# Sch1.net
KiCad netlist of a schematic drawn in EAGLE
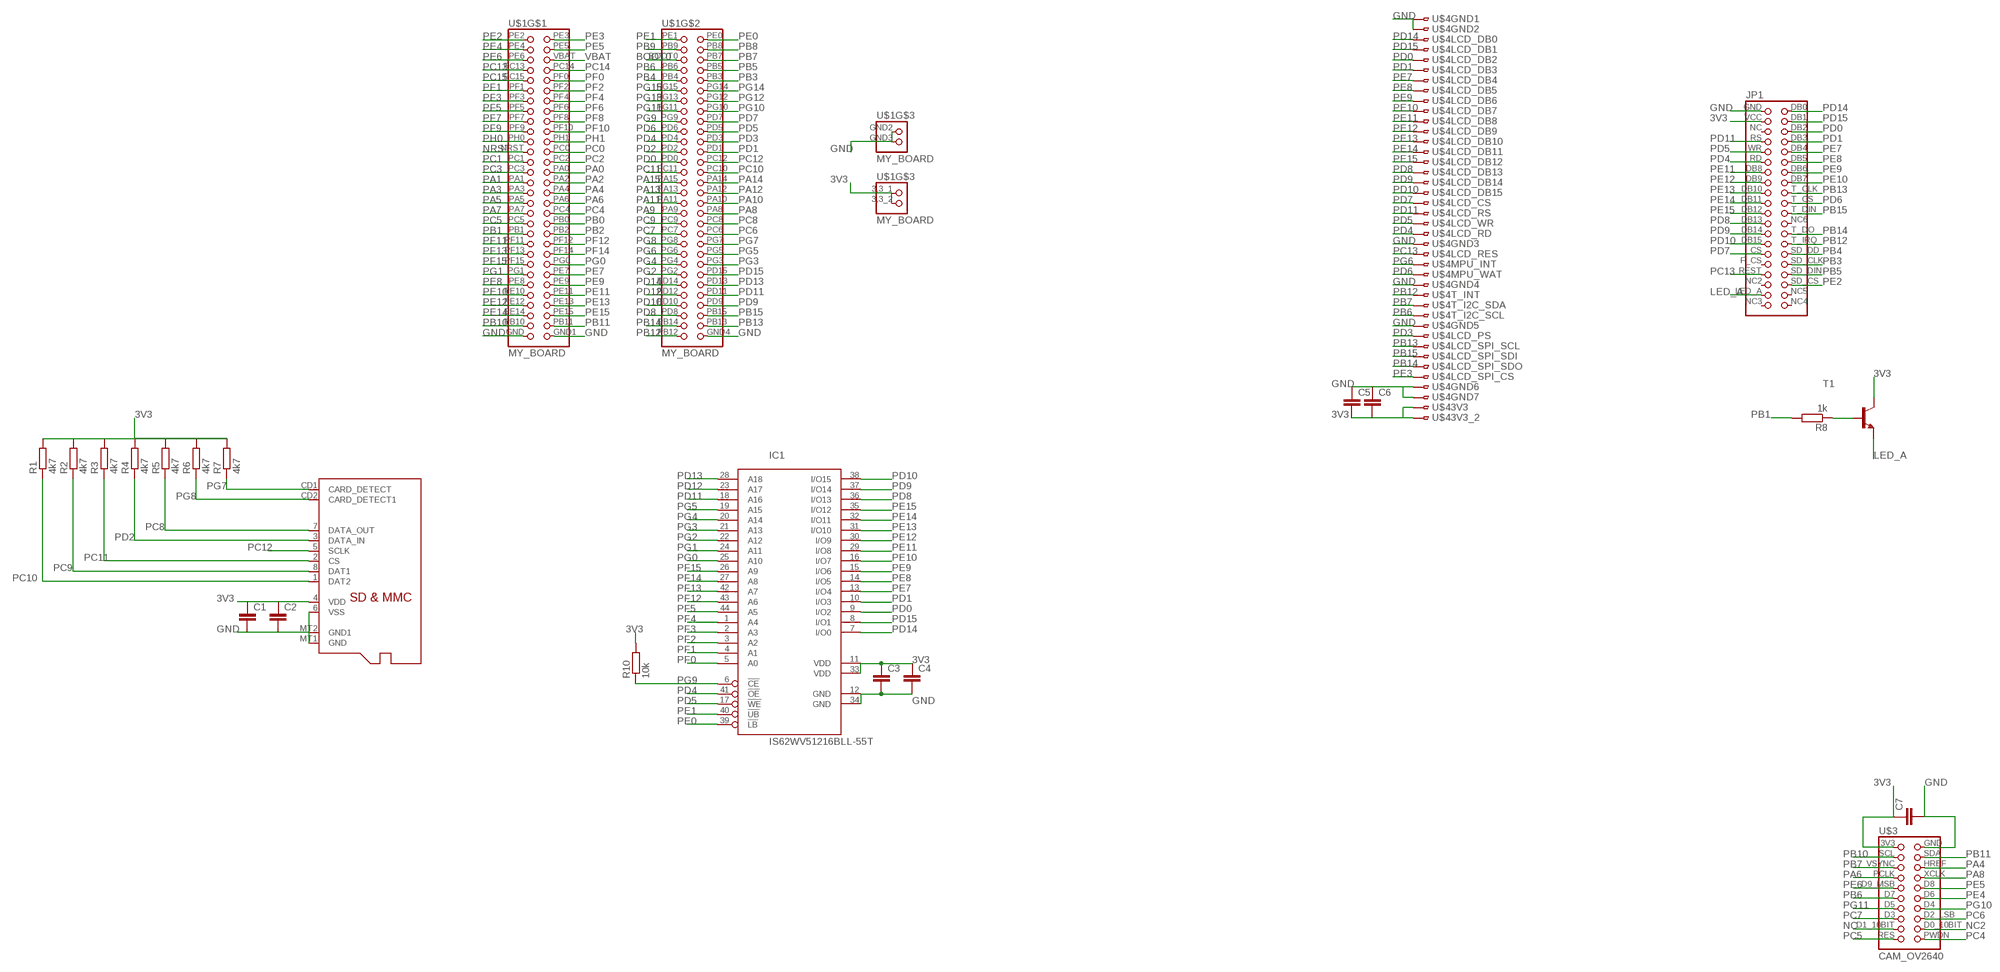
[diagram p0: schematic, sheet 1]

(export (version "E")
  (design (tool "Eeschema 10.0.6"))
  (components
    (comp (ref "C1")
      (value "C-EUC1206")
      (footprint "eagle-import:C1206")
      (libsource (lib "eagle-import") (part "C-EUC1206"))
    )
    (comp (ref "C2")
      (value "C-EUC1206")
      (footprint "eagle-import:C1206")
      (libsource (lib "eagle-import") (part "C-EUC1206"))
    )
    (comp (ref "C3")
      (value "C-EUC1206")
      (footprint "eagle-import:C1206")
      (libsource (lib "eagle-import") (part "C-EUC1206"))
    )
    (comp (ref "C4")
      (value "C-EUC1206")
      (footprint "eagle-import:C1206")
      (libsource (lib "eagle-import") (part "C-EUC1206"))
    )
    (comp (ref "C5")
      (value "C-EUC1206")
      (footprint "eagle-import:C1206")
      (libsource (lib "eagle-import") (part "C-EUC1206"))
    )
    (comp (ref "C6")
      (value "C-EUC1206")
      (footprint "eagle-import:C1206")
      (libsource (lib "eagle-import") (part "C-EUC1206"))
    )
    (comp (ref "C7")
      (value "C-EUC1206")
      (footprint "eagle-import:C1206")
      (libsource (lib "eagle-import") (part "C-EUC1206"))
    )
    (comp (ref "IC1")
      (value "IS62WV51216BLL-55T")
      (footprint "eagle-import:TSOP-II-44")
      (libsource (lib "eagle-import") (part "IS62WV51216BLL-T55"))
    )
    (comp (ref "JP1")
      (value "LCD320QVBLCD320QVB")
      (footprint "eagle-import:2X20")
      (libsource (lib "eagle-import") (part "LCD320QVBLCD320QVB"))
    )
    (comp (ref "R1")
      (value "4k7")
      (footprint "eagle-import:0204_7")
      (libsource (lib "eagle-import") (part "resistor_R-EU_0204/7"))
    )
    (comp (ref "R2")
      (value "4k7")
      (footprint "eagle-import:0204_7")
      (libsource (lib "eagle-import") (part "resistor_R-EU_0204/7"))
    )
    (comp (ref "R3")
      (value "4k7")
      (footprint "eagle-import:0204_7")
      (libsource (lib "eagle-import") (part "resistor_R-EU_0204/7"))
    )
    (comp (ref "R4")
      (value "4k7")
      (footprint "eagle-import:0204_7")
      (libsource (lib "eagle-import") (part "resistor_R-EU_0204/7"))
    )
    (comp (ref "R5")
      (value "4k7")
      (footprint "eagle-import:0204_7")
      (libsource (lib "eagle-import") (part "resistor_R-EU_0204/7"))
    )
    (comp (ref "R6")
      (value "4k7")
      (footprint "eagle-import:0204_7")
      (libsource (lib "eagle-import") (part "resistor_R-EU_0204/7"))
    )
    (comp (ref "R7")
      (value "4k7")
      (footprint "eagle-import:0204_7")
      (libsource (lib "eagle-import") (part "resistor_R-EU_0204/7"))
    )
    (comp (ref "R8")
      (value "1k")
      (footprint "eagle-import:0204_5")
      (libsource (lib "eagle-import") (part "R-EU_0204/5"))
    )
    (comp (ref "R10")
      (value "10k")
      (footprint "eagle-import:0204_7")
      (libsource (lib "eagle-import") (part "resistor_R-EU_0204/7"))
    )
    (comp (ref "T1")
      (value "BC337-NPN-TO92-CBE")
      (footprint "eagle-import:TO92-CBE")
      (libsource (lib "eagle-import") (part "-NPN-TO92-CBEBC337"))
    )
    (comp (ref "U$1")
      (value "MY_BOARD")
      (footprint "eagle-import:MY_BOARD")
      (libsource (lib "eagle-import") (part "MY_BOARD"))
    )
    (comp (ref "U$3")
      (value "CAM_OV2640")
      (footprint "eagle-import:CAM_OV2640")
      (libsource (lib "eagle-import") (part "CAM_OV2640"))
    )
    (comp (ref "U$4")
      (value "LCD800TFT")
      (footprint "eagle-import:FH12-40S-0.5SH")
      (libsource (lib "eagle-import") (part "LCD800TFT"))
    )
    (comp (ref "U$5")
      (value "MICROSD")
      (footprint "eagle-import:MICROSD")
      (libsource (lib "eagle-import") (part "MICROSD"))
    )
  )
  (nets
    (net (code "1") (name "/3V3") (class "Default")
      (node (ref "C1") (pin "1") (pinfunction "1_1") (pintype "passive"))
      (node (ref "C2") (pin "1") (pinfunction "1_1") (pintype "passive"))
      (node (ref "C3") (pin "1") (pinfunction "1_1") (pintype "passive"))
      (node (ref "C4") (pin "1") (pinfunction "1_1") (pintype "passive"))
      (node (ref "C5") (pin "2") (pinfunction "2_2") (pintype "passive"))
      (node (ref "C6") (pin "2") (pinfunction "2_2") (pintype "passive"))
      (node (ref "C7") (pin "1") (pinfunction "1_1") (pintype "passive"))
      (node (ref "IC1") (pin "11") (pinfunction "VDD_11") (pintype "power_in"))
      (node (ref "IC1") (pin "33") (pinfunction "VDD_33") (pintype "power_in"))
      (node (ref "JP1") (pin "VCC") (pinfunction "3_VCC") (pintype "passive"))
      (node (ref "R1") (pin "2") (pinfunction "2_2") (pintype "passive"))
      (node (ref "R10") (pin "2") (pinfunction "2_2") (pintype "passive"))
      (node (ref "R2") (pin "2") (pinfunction "2_2") (pintype "passive"))
      (node (ref "R3") (pin "2") (pinfunction "2_2") (pintype "passive"))
      (node (ref "R4") (pin "2") (pinfunction "2_2") (pintype "passive"))
      (node (ref "R5") (pin "2") (pinfunction "2_2") (pintype "passive"))
      (node (ref "R6") (pin "2") (pinfunction "2_2") (pintype "passive"))
      (node (ref "R7") (pin "2") (pinfunction "2_2") (pintype "passive"))
      (node (ref "T1") (pin "C") (pinfunction "C_C") (pintype "passive"))
      (node (ref "U$1") (pin "3,3_1") (pinfunction "1_3,3_1") (pintype "passive"))
      (node (ref "U$1") (pin "3,3_2") (pinfunction "2_3,3_2") (pintype "passive"))
      (node (ref "U$3") (pin "3V3") (pinfunction "3V3_3V3") (pintype "passive"))
      (node (ref "U$4") (pin "39") (pinfunction "1_39") (pintype "passive"))
      (node (ref "U$4") (pin "40") (pinfunction "1_40") (pintype "passive"))
      (node (ref "U$5") (pin "4") (pinfunction "VDD_4") (pintype "power_in"))
    )
    (net (code "2") (name "/BOOT0") (class "Default")
      (node (ref "U$1") (pin "BOOT0") (pinfunction "5_BOOT0") (pintype "passive"))
    )
    (net (code "3") (name "/GND") (class "Default")
      (node (ref "C1") (pin "2") (pinfunction "2_2") (pintype "passive"))
      (node (ref "C2") (pin "2") (pinfunction "2_2") (pintype "passive"))
      (node (ref "C3") (pin "2") (pinfunction "2_2") (pintype "passive"))
      (node (ref "C4") (pin "2") (pinfunction "2_2") (pintype "passive"))
      (node (ref "C5") (pin "1") (pinfunction "1_1") (pintype "passive"))
      (node (ref "C6") (pin "1") (pinfunction "1_1") (pintype "passive"))
      (node (ref "C7") (pin "2") (pinfunction "2_2") (pintype "passive"))
      (node (ref "IC1") (pin "12") (pinfunction "GND_12") (pintype "power_in"))
      (node (ref "IC1") (pin "34") (pinfunction "GND_34") (pintype "power_in"))
      (node (ref "JP1") (pin "GND") (pinfunction "1_GND") (pintype "passive"))
      (node (ref "U$1") (pin "GND") (pinfunction "59_GND") (pintype "passive"))
      (node (ref "U$1") (pin "GND1") (pinfunction "60_GND1") (pintype "passive"))
      (node (ref "U$1") (pin "GND2") (pinfunction "3_GND2") (pintype "passive"))
      (node (ref "U$1") (pin "GND3") (pinfunction "4_GND3") (pintype "passive"))
      (node (ref "U$1") (pin "GND4") (pinfunction "60_GND4") (pintype "passive"))
      (node (ref "U$3") (pin "GND") (pinfunction "GND_GND") (pintype "passive"))
      (node (ref "U$4") (pin "1") (pinfunction "1_1") (pintype "passive"))
      (node (ref "U$4") (pin "2") (pinfunction "1_2") (pintype "passive"))
      (node (ref "U$4") (pin "23") (pinfunction "1_23") (pintype "passive"))
      (node (ref "U$4") (pin "27") (pinfunction "1_27") (pintype "passive"))
      (node (ref "U$4") (pin "31") (pinfunction "1_31") (pintype "passive"))
      (node (ref "U$4") (pin "37") (pinfunction "1_37") (pintype "passive"))
      (node (ref "U$4") (pin "38") (pinfunction "1_38") (pintype "passive"))
      (node (ref "U$5") (pin "6") (pinfunction "VSS_6") (pintype "power_in"))
      (node (ref "U$5") (pin "MT1") (pinfunction "GND_MT1") (pintype "power_in"))
      (node (ref "U$5") (pin "MT2") (pinfunction "GND1_MT2") (pintype "power_in"))
    )
    (net (code "4") (name "/LED_A") (class "Default")
      (node (ref "JP1") (pin "LED_A") (pinfunction "37_LED_A") (pintype "passive"))
      (node (ref "T1") (pin "E") (pinfunction "E_E") (pintype "passive"))
    )
    (net (code "5") (name "/NC") (class "Default")
      (node (ref "U$3") (pin "D1_10BIT") (pinfunction "D1_10BIT_D1_10BIT") (pintype "passive"))
    )
    (net (code "6") (name "/NC2") (class "Default")
      (node (ref "U$3") (pin "D0_10BIT") (pinfunction "D0_10BIT_D0_10BIT") (pintype "passive"))
    )
    (net (code "7") (name "/NRST") (class "Default")
      (node (ref "U$1") (pin "NRST") (pinfunction "23_NRST") (pintype "passive"))
    )
    (net (code "8") (name "/PA0") (class "Default")
      (node (ref "U$1") (pin "PA0") (pinfunction "28_PA0") (pintype "passive"))
    )
    (net (code "9") (name "/PA1") (class "Default")
      (node (ref "U$1") (pin "PA1") (pinfunction "29_PA1") (pintype "passive"))
    )
    (net (code "10") (name "/PA2") (class "Default")
      (node (ref "U$1") (pin "PA2") (pinfunction "30_PA2") (pintype "passive"))
    )
    (net (code "11") (name "/PA3") (class "Default")
      (node (ref "U$1") (pin "PA3") (pinfunction "31_PA3") (pintype "passive"))
    )
    (net (code "12") (name "/PA4") (class "Default")
      (node (ref "U$1") (pin "PA4") (pinfunction "32_PA4") (pintype "passive"))
      (node (ref "U$3") (pin "HREF") (pinfunction "HREF_HREF") (pintype "passive"))
    )
    (net (code "13") (name "/PA5") (class "Default")
      (node (ref "U$1") (pin "PA5") (pinfunction "33_PA5") (pintype "passive"))
    )
    (net (code "14") (name "/PA6") (class "Default")
      (node (ref "U$1") (pin "PA6") (pinfunction "34_PA6") (pintype "passive"))
      (node (ref "U$3") (pin "PCLK") (pinfunction "PCLK_PCLK") (pintype "passive"))
    )
    (net (code "15") (name "/PA7") (class "Default")
      (node (ref "U$1") (pin "PA7") (pinfunction "35_PA7") (pintype "passive"))
    )
    (net (code "16") (name "/PA8") (class "Default")
      (node (ref "U$1") (pin "PA8") (pinfunction "36_PA8") (pintype "passive"))
      (node (ref "U$3") (pin "XCLK") (pinfunction "XCLK_XCLK") (pintype "passive"))
    )
    (net (code "17") (name "/PA9") (class "Default")
      (node (ref "U$1") (pin "PA9") (pinfunction "35_PA9") (pintype "passive"))
    )
    (net (code "18") (name "/PA10") (class "Default")
      (node (ref "U$1") (pin "PA10") (pinfunction "34_PA10") (pintype "passive"))
    )
    (net (code "19") (name "/PA11") (class "Default")
      (node (ref "U$1") (pin "PA11") (pinfunction "33_PA11") (pintype "passive"))
    )
    (net (code "20") (name "/PA12") (class "Default")
      (node (ref "U$1") (pin "PA12") (pinfunction "32_PA12") (pintype "passive"))
    )
    (net (code "21") (name "/PA13") (class "Default")
      (node (ref "U$1") (pin "PA13") (pinfunction "31_PA13") (pintype "passive"))
    )
    (net (code "22") (name "/PA14") (class "Default")
      (node (ref "U$1") (pin "PA14") (pinfunction "30_PA14") (pintype "passive"))
    )
    (net (code "23") (name "/PA15") (class "Default")
      (node (ref "U$1") (pin "PA15") (pinfunction "29_PA15") (pintype "passive"))
    )
    (net (code "24") (name "/PB0") (class "Default")
      (node (ref "U$1") (pin "PB0") (pinfunction "38_PB0") (pintype "passive"))
    )
    (net (code "25") (name "/PB1") (class "Default")
      (node (ref "R8") (pin "2") (pinfunction "2_2") (pintype "passive"))
      (node (ref "U$1") (pin "PB1") (pinfunction "39_PB1") (pintype "passive"))
    )
    (net (code "26") (name "/PB2") (class "Default")
      (node (ref "U$1") (pin "PB2") (pinfunction "40_PB2") (pintype "passive"))
    )
    (net (code "27") (name "/PB3") (class "Default")
      (node (ref "JP1") (pin "SD_CLK") (pinfunction "32_SD_CLK") (pintype "passive"))
      (node (ref "U$1") (pin "PB3") (pinfunction "10_PB3") (pintype "passive"))
    )
    (net (code "28") (name "/PB4") (class "Default")
      (node (ref "JP1") (pin "SD_DD") (pinfunction "30_SD_DD") (pintype "passive"))
      (node (ref "U$1") (pin "PB4") (pinfunction "9_PB4") (pintype "passive"))
    )
    (net (code "29") (name "/PB5") (class "Default")
      (node (ref "JP1") (pin "SD_DIN") (pinfunction "34_SD_DIN") (pintype "passive"))
      (node (ref "U$1") (pin "PB5") (pinfunction "8_PB5") (pintype "passive"))
    )
    (net (code "30") (name "/PB6") (class "Default")
      (node (ref "U$1") (pin "PB6") (pinfunction "7_PB6") (pintype "passive"))
      (node (ref "U$3") (pin "D7") (pinfunction "D7_D7") (pintype "passive"))
      (node (ref "U$4") (pin "30") (pinfunction "1_30") (pintype "passive"))
    )
    (net (code "31") (name "/PB7") (class "Default")
      (node (ref "U$1") (pin "PB7") (pinfunction "6_PB7") (pintype "passive"))
      (node (ref "U$3") (pin "VSYNC") (pinfunction "VSYNC_VSYNC") (pintype "passive"))
      (node (ref "U$4") (pin "29") (pinfunction "1_29") (pintype "passive"))
    )
    (net (code "32") (name "/PB8") (class "Default")
      (node (ref "U$1") (pin "PB8") (pinfunction "4_PB8") (pintype "passive"))
    )
    (net (code "33") (name "/PB9") (class "Default")
      (node (ref "U$1") (pin "PB9") (pinfunction "3_PB9") (pintype "passive"))
    )
    (net (code "34") (name "/PB10") (class "Default")
      (node (ref "U$1") (pin "PB10") (pinfunction "57_PB10") (pintype "passive"))
      (node (ref "U$3") (pin "SCL") (pinfunction "SCL_SCL") (pintype "passive"))
    )
    (net (code "35") (name "/PB11") (class "Default")
      (node (ref "U$1") (pin "PB11") (pinfunction "58_PB11") (pintype "passive"))
      (node (ref "U$3") (pin "SDA") (pinfunction "SDA_SDA") (pintype "passive"))
    )
    (net (code "36") (name "/PB12") (class "Default")
      (node (ref "JP1") (pin "T_IRQ") (pinfunction "28_T_IRQ") (pintype "passive"))
      (node (ref "U$1") (pin "PB12") (pinfunction "59_PB12") (pintype "passive"))
      (node (ref "U$4") (pin "28") (pinfunction "1_28") (pintype "passive"))
    )
    (net (code "37") (name "/PB13") (class "Default")
      (node (ref "JP1") (pin "T_CLK") (pinfunction "18_T_CLK") (pintype "passive"))
      (node (ref "U$1") (pin "PB13") (pinfunction "58_PB13") (pintype "passive"))
      (node (ref "U$4") (pin "33") (pinfunction "1_33") (pintype "passive"))
    )
    (net (code "38") (name "/PB14") (class "Default")
      (node (ref "JP1") (pin "T_DO") (pinfunction "26_T_DO") (pintype "passive"))
      (node (ref "U$1") (pin "PB14") (pinfunction "57_PB14") (pintype "passive"))
      (node (ref "U$4") (pin "35") (pinfunction "1_35") (pintype "passive"))
    )
    (net (code "39") (name "/PB15") (class "Default")
      (node (ref "JP1") (pin "T_DIN") (pinfunction "22_T_DIN") (pintype "passive"))
      (node (ref "U$1") (pin "PB15") (pinfunction "56_PB15") (pintype "passive"))
      (node (ref "U$4") (pin "34") (pinfunction "1_34") (pintype "passive"))
    )
    (net (code "40") (name "/PC0") (class "Default")
      (node (ref "U$1") (pin "PC0") (pinfunction "24_PC0") (pintype "passive"))
    )
    (net (code "41") (name "/PC1") (class "Default")
      (node (ref "U$1") (pin "PC1") (pinfunction "25_PC1") (pintype "passive"))
    )
    (net (code "42") (name "/PC2") (class "Default")
      (node (ref "U$1") (pin "PC2") (pinfunction "26_PC2") (pintype "passive"))
    )
    (net (code "43") (name "/PC3") (class "Default")
      (node (ref "U$1") (pin "PC3") (pinfunction "27_PC3") (pintype "passive"))
    )
    (net (code "44") (name "/PC4") (class "Default")
      (node (ref "U$1") (pin "PC4") (pinfunction "36_PC4") (pintype "passive"))
      (node (ref "U$3") (pin "PWDN") (pinfunction "PWDN_PWDN") (pintype "passive"))
    )
    (net (code "45") (name "/PC5") (class "Default")
      (node (ref "U$1") (pin "PC5") (pinfunction "37_PC5") (pintype "passive"))
      (node (ref "U$3") (pin "RES") (pinfunction "RES_RES") (pintype "passive"))
    )
    (net (code "46") (name "/PC6") (class "Default")
      (node (ref "U$1") (pin "PC6") (pinfunction "40_PC6") (pintype "passive"))
      (node (ref "U$3") (pin "D2_LSB") (pinfunction "D2_LSB_D2_LSB") (pintype "passive"))
    )
    (net (code "47") (name "/PC7") (class "Default")
      (node (ref "U$1") (pin "PC7") (pinfunction "39_PC7") (pintype "passive"))
      (node (ref "U$3") (pin "D3") (pinfunction "D3_D3") (pintype "passive"))
    )
    (net (code "48") (name "/PC8") (class "Default")
      (node (ref "R5") (pin "1") (pinfunction "1_1") (pintype "passive"))
      (node (ref "U$1") (pin "PC8") (pinfunction "38_PC8") (pintype "passive"))
      (node (ref "U$5") (pin "7") (pinfunction "DATA_OUT_7") (pintype "output"))
    )
    (net (code "49") (name "/PC9") (class "Default")
      (node (ref "R2") (pin "1") (pinfunction "1_1") (pintype "passive"))
      (node (ref "U$1") (pin "PC9") (pinfunction "37_PC9") (pintype "passive"))
      (node (ref "U$5") (pin "8") (pinfunction "DAT1_8") (pintype "bidirectional"))
    )
    (net (code "50") (name "/PC10") (class "Default")
      (node (ref "R1") (pin "1") (pinfunction "1_1") (pintype "passive"))
      (node (ref "U$1") (pin "PC10") (pinfunction "28_PC10") (pintype "passive"))
      (node (ref "U$5") (pin "1") (pinfunction "DAT2_1") (pintype "bidirectional"))
    )
    (net (code "51") (name "/PC11") (class "Default")
      (node (ref "R3") (pin "1") (pinfunction "1_1") (pintype "passive"))
      (node (ref "U$1") (pin "PC11") (pinfunction "27_PC11") (pintype "passive"))
      (node (ref "U$5") (pin "2") (pinfunction "CS_2") (pintype "input"))
    )
    (net (code "52") (name "/PC12") (class "Default")
      (node (ref "U$1") (pin "PC12") (pinfunction "26_PC12") (pintype "passive"))
      (node (ref "U$5") (pin "5") (pinfunction "SCLK_5") (pintype "input"))
    )
    (net (code "53") (name "/PC13") (class "Default")
      (node (ref "JP1") (pin "REST") (pinfunction "33_REST") (pintype "passive"))
      (node (ref "U$1") (pin "PC13") (pinfunction "7_PC13") (pintype "passive"))
      (node (ref "U$4") (pin "24") (pinfunction "1_24") (pintype "passive"))
    )
    (net (code "54") (name "/PC14") (class "Default")
      (node (ref "U$1") (pin "PC14") (pinfunction "8_PC14") (pintype "passive"))
    )
    (net (code "55") (name "/PC15") (class "Default")
      (node (ref "U$1") (pin "PC15") (pinfunction "9_PC15") (pintype "passive"))
    )
    (net (code "56") (name "/PD0") (class "Default")
      (node (ref "IC1") (pin "9") (pinfunction "I/O2_9") (pintype "tri_state"))
      (node (ref "JP1") (pin "DB2") (pinfunction "6_DB2") (pintype "passive"))
      (node (ref "U$1") (pin "PD0") (pinfunction "25_PD0") (pintype "passive"))
      (node (ref "U$4") (pin "5") (pinfunction "1_5") (pintype "passive"))
    )
    (net (code "57") (name "/PD1") (class "Default")
      (node (ref "IC1") (pin "10") (pinfunction "I/O3_10") (pintype "tri_state"))
      (node (ref "JP1") (pin "DB3") (pinfunction "8_DB3") (pintype "passive"))
      (node (ref "U$1") (pin "PD1") (pinfunction "24_PD1") (pintype "passive"))
      (node (ref "U$4") (pin "6") (pinfunction "1_6") (pintype "passive"))
    )
    (net (code "58") (name "/PD2") (class "Default")
      (node (ref "R4") (pin "1") (pinfunction "1_1") (pintype "passive"))
      (node (ref "U$1") (pin "PD2") (pinfunction "23_PD2") (pintype "passive"))
      (node (ref "U$5") (pin "3") (pinfunction "DATA_IN_3") (pintype "input"))
    )
    (net (code "59") (name "/PD3") (class "Default")
      (node (ref "U$1") (pin "PD3") (pinfunction "22_PD3") (pintype "passive"))
      (node (ref "U$4") (pin "32") (pinfunction "1_32") (pintype "passive"))
    )
    (net (code "60") (name "/PD4") (class "Default")
      (node (ref "IC1") (pin "41") (pinfunction "~{OE}_41") (pintype "input"))
      (node (ref "JP1") (pin "RD") (pinfunction "11_RD") (pintype "passive"))
      (node (ref "U$1") (pin "PD4") (pinfunction "21_PD4") (pintype "passive"))
      (node (ref "U$4") (pin "22") (pinfunction "1_22") (pintype "passive"))
    )
    (net (code "61") (name "/PD5") (class "Default")
      (node (ref "IC1") (pin "17") (pinfunction "~{WE}_17") (pintype "input"))
      (node (ref "JP1") (pin "WR") (pinfunction "9_WR") (pintype "passive"))
      (node (ref "U$1") (pin "PD5") (pinfunction "20_PD5") (pintype "passive"))
      (node (ref "U$4") (pin "21") (pinfunction "1_21") (pintype "passive"))
    )
    (net (code "62") (name "/PD6") (class "Default")
      (node (ref "JP1") (pin "T_CS") (pinfunction "20_T_CS") (pintype "passive"))
      (node (ref "U$1") (pin "PD6") (pinfunction "19_PD6") (pintype "passive"))
      (node (ref "U$4") (pin "26") (pinfunction "1_26") (pintype "passive"))
    )
    (net (code "63") (name "/PD7") (class "Default")
      (node (ref "JP1") (pin "CS") (pinfunction "29_CS") (pintype "passive"))
      (node (ref "U$1") (pin "PD7") (pinfunction "18_PD7") (pintype "passive"))
      (node (ref "U$4") (pin "19") (pinfunction "1_19") (pintype "passive"))
    )
    (net (code "64") (name "/PD8") (class "Default")
      (node (ref "IC1") (pin "36") (pinfunction "I/O13_36") (pintype "tri_state"))
      (node (ref "JP1") (pin "DB13") (pinfunction "23_DB13") (pintype "passive"))
      (node (ref "U$1") (pin "PD8") (pinfunction "55_PD8") (pintype "passive"))
      (node (ref "U$4") (pin "16") (pinfunction "1_16") (pintype "passive"))
    )
    (net (code "65") (name "/PD9") (class "Default")
      (node (ref "IC1") (pin "37") (pinfunction "I/O14_37") (pintype "tri_state"))
      (node (ref "JP1") (pin "DB14") (pinfunction "25_DB14") (pintype "passive"))
      (node (ref "U$1") (pin "PD9") (pinfunction "54_PD9") (pintype "passive"))
      (node (ref "U$4") (pin "17") (pinfunction "1_17") (pintype "passive"))
    )
    (net (code "66") (name "/PD10") (class "Default")
      (node (ref "IC1") (pin "38") (pinfunction "I/O15_38") (pintype "tri_state"))
      (node (ref "JP1") (pin "DB15") (pinfunction "27_DB15") (pintype "passive"))
      (node (ref "U$1") (pin "PD10") (pinfunction "53_PD10") (pintype "passive"))
      (node (ref "U$4") (pin "18") (pinfunction "1_18") (pintype "passive"))
    )
    (net (code "67") (name "/PD11") (class "Default")
      (node (ref "IC1") (pin "18") (pinfunction "A16_18") (pintype "input"))
      (node (ref "JP1") (pin "RS") (pinfunction "7_RS") (pintype "passive"))
      (node (ref "U$1") (pin "PD11") (pinfunction "52_PD11") (pintype "passive"))
      (node (ref "U$4") (pin "20") (pinfunction "1_20") (pintype "passive"))
    )
    (net (code "68") (name "/PD12") (class "Default")
      (node (ref "IC1") (pin "23") (pinfunction "A17_23") (pintype "input"))
      (node (ref "U$1") (pin "PD12") (pinfunction "51_PD12") (pintype "passive"))
    )
    (net (code "69") (name "/PD13") (class "Default")
      (node (ref "IC1") (pin "28") (pinfunction "A18_28") (pintype "input"))
      (node (ref "U$1") (pin "PD13") (pinfunction "50_PD13") (pintype "passive"))
    )
    (net (code "70") (name "/PD14") (class "Default")
      (node (ref "IC1") (pin "7") (pinfunction "I/O0_7") (pintype "tri_state"))
      (node (ref "JP1") (pin "DB0") (pinfunction "2_DB0") (pintype "passive"))
      (node (ref "U$1") (pin "PD14") (pinfunction "49_PD14") (pintype "passive"))
      (node (ref "U$4") (pin "3") (pinfunction "1_3") (pintype "passive"))
    )
    (net (code "71") (name "/PD15") (class "Default")
      (node (ref "IC1") (pin "8") (pinfunction "I/O1_8") (pintype "tri_state"))
      (node (ref "JP1") (pin "DB1") (pinfunction "4_DB1") (pintype "passive"))
      (node (ref "U$1") (pin "PD15") (pinfunction "48_PD15") (pintype "passive"))
      (node (ref "U$4") (pin "4") (pinfunction "1_4") (pintype "passive"))
    )
    (net (code "72") (name "/PE0") (class "Default")
      (node (ref "IC1") (pin "39") (pinfunction "~{LB}_39") (pintype "input"))
      (node (ref "U$1") (pin "PE0") (pinfunction "2_PE0") (pintype "passive"))
    )
    (net (code "73") (name "/PE1") (class "Default")
      (node (ref "IC1") (pin "40") (pinfunction "~{UB}_40") (pintype "input"))
      (node (ref "U$1") (pin "PE1") (pinfunction "1_PE1") (pintype "passive"))
    )
    (net (code "74") (name "/PE2") (class "Default")
      (node (ref "JP1") (pin "SD_CS") (pinfunction "36_SD_CS") (pintype "passive"))
      (node (ref "U$1") (pin "PE2") (pinfunction "1_PE2") (pintype "passive"))
    )
    (net (code "75") (name "/PE3") (class "Default")
      (node (ref "U$1") (pin "PE3") (pinfunction "2_PE3") (pintype "passive"))
      (node (ref "U$4") (pin "36") (pinfunction "1_36") (pintype "passive"))
    )
    (net (code "76") (name "/PE4") (class "Default")
      (node (ref "U$1") (pin "PE4") (pinfunction "3_PE4") (pintype "passive"))
      (node (ref "U$3") (pin "D6") (pinfunction "D6_D6") (pintype "passive"))
    )
    (net (code "77") (name "/PE5") (class "Default")
      (node (ref "U$1") (pin "PE5") (pinfunction "4_PE5") (pintype "passive"))
      (node (ref "U$3") (pin "D8") (pinfunction "D8_D8") (pintype "passive"))
    )
    (net (code "78") (name "/PE6") (class "Default")
      (node (ref "U$1") (pin "PE6") (pinfunction "5_PE6") (pintype "passive"))
      (node (ref "U$3") (pin "D9_MSB") (pinfunction "D9_MSB_D9_MSB") (pintype "passive"))
    )
    (net (code "79") (name "/PE7") (class "Default")
      (node (ref "IC1") (pin "13") (pinfunction "I/O4_13") (pintype "tri_state"))
      (node (ref "JP1") (pin "DB4") (pinfunction "10_DB4") (pintype "passive"))
      (node (ref "U$1") (pin "PE7") (pinfunction "48_PE7") (pintype "passive"))
      (node (ref "U$4") (pin "7") (pinfunction "1_7") (pintype "passive"))
    )
    (net (code "80") (name "/PE8") (class "Default")
      (node (ref "IC1") (pin "14") (pinfunction "I/O5_14") (pintype "tri_state"))
      (node (ref "JP1") (pin "DB5") (pinfunction "12_DB5") (pintype "passive"))
      (node (ref "U$1") (pin "PE8") (pinfunction "49_PE8") (pintype "passive"))
      (node (ref "U$4") (pin "8") (pinfunction "1_8") (pintype "passive"))
    )
    (net (code "81") (name "/PE9") (class "Default")
      (node (ref "IC1") (pin "15") (pinfunction "I/O6_15") (pintype "tri_state"))
      (node (ref "JP1") (pin "DB6") (pinfunction "14_DB6") (pintype "passive"))
      (node (ref "U$1") (pin "PE9") (pinfunction "50_PE9") (pintype "passive"))
      (node (ref "U$4") (pin "9") (pinfunction "1_9") (pintype "passive"))
    )
    (net (code "82") (name "/PE10") (class "Default")
      (node (ref "IC1") (pin "16") (pinfunction "I/O7_16") (pintype "tri_state"))
      (node (ref "JP1") (pin "DB7") (pinfunction "16_DB7") (pintype "passive"))
      (node (ref "U$1") (pin "PE10") (pinfunction "51_PE10") (pintype "passive"))
      (node (ref "U$4") (pin "10") (pinfunction "1_10") (pintype "passive"))
    )
    (net (code "83") (name "/PE11") (class "Default")
      (node (ref "IC1") (pin "29") (pinfunction "I/O8_29") (pintype "tri_state"))
      (node (ref "JP1") (pin "DB8") (pinfunction "13_DB8") (pintype "passive"))
      (node (ref "U$1") (pin "PE11") (pinfunction "52_PE11") (pintype "passive"))
      (node (ref "U$4") (pin "11") (pinfunction "1_11") (pintype "passive"))
    )
    (net (code "84") (name "/PE12") (class "Default")
      (node (ref "IC1") (pin "30") (pinfunction "I/O9_30") (pintype "tri_state"))
      (node (ref "JP1") (pin "DB9") (pinfunction "15_DB9") (pintype "passive"))
      (node (ref "U$1") (pin "PE12") (pinfunction "53_PE12") (pintype "passive"))
      (node (ref "U$4") (pin "12") (pinfunction "1_12") (pintype "passive"))
    )
    (net (code "85") (name "/PE13") (class "Default")
      (node (ref "IC1") (pin "31") (pinfunction "I/O10_31") (pintype "tri_state"))
      (node (ref "JP1") (pin "DB10") (pinfunction "17_DB10") (pintype "passive"))
      (node (ref "U$1") (pin "PE13") (pinfunction "54_PE13") (pintype "passive"))
      (node (ref "U$4") (pin "13") (pinfunction "1_13") (pintype "passive"))
    )
    (net (code "86") (name "/PE14") (class "Default")
      (node (ref "IC1") (pin "32") (pinfunction "I/O11_32") (pintype "tri_state"))
      (node (ref "JP1") (pin "DB11") (pinfunction "19_DB11") (pintype "passive"))
      (node (ref "U$1") (pin "PE14") (pinfunction "55_PE14") (pintype "passive"))
      (node (ref "U$4") (pin "14") (pinfunction "1_14") (pintype "passive"))
    )
    (net (code "87") (name "/PE15") (class "Default")
      (node (ref "IC1") (pin "35") (pinfunction "I/O12_35") (pintype "tri_state"))
      (node (ref "JP1") (pin "DB12") (pinfunction "21_DB12") (pintype "passive"))
      (node (ref "U$1") (pin "PE15") (pinfunction "56_PE15") (pintype "passive"))
      (node (ref "U$4") (pin "15") (pinfunction "1_15") (pintype "passive"))
    )
    (net (code "88") (name "/PF0") (class "Default")
      (node (ref "IC1") (pin "5") (pinfunction "A0_5") (pintype "input"))
      (node (ref "U$1") (pin "PF0") (pinfunction "10_PF0") (pintype "passive"))
    )
    (net (code "89") (name "/PF1") (class "Default")
      (node (ref "IC1") (pin "4") (pinfunction "A1_4") (pintype "input"))
      (node (ref "U$1") (pin "PF1") (pinfunction "11_PF1") (pintype "passive"))
    )
    (net (code "90") (name "/PF2") (class "Default")
      (node (ref "IC1") (pin "3") (pinfunction "A2_3") (pintype "input"))
      (node (ref "U$1") (pin "PF2") (pinfunction "12_PF2") (pintype "passive"))
    )
    (net (code "91") (name "/PF3") (class "Default")
      (node (ref "IC1") (pin "2") (pinfunction "A3_2") (pintype "input"))
      (node (ref "U$1") (pin "PF3") (pinfunction "13_PF3") (pintype "passive"))
    )
    (net (code "92") (name "/PF4") (class "Default")
      (node (ref "IC1") (pin "1") (pinfunction "A4_1") (pintype "input"))
      (node (ref "U$1") (pin "PF4") (pinfunction "14_PF4") (pintype "passive"))
    )
    (net (code "93") (name "/PF5") (class "Default")
      (node (ref "IC1") (pin "44") (pinfunction "A5_44") (pintype "input"))
      (node (ref "U$1") (pin "PF5") (pinfunction "15_PF5") (pintype "passive"))
    )
    (net (code "94") (name "/PF6") (class "Default")
      (node (ref "U$1") (pin "PF6") (pinfunction "16_PF6") (pintype "passive"))
    )
    (net (code "95") (name "/PF7") (class "Default")
      (node (ref "U$1") (pin "PF7") (pinfunction "17_PF7") (pintype "passive"))
    )
    (net (code "96") (name "/PF8") (class "Default")
      (node (ref "U$1") (pin "PF8") (pinfunction "18_PF8") (pintype "passive"))
    )
    (net (code "97") (name "/PF9") (class "Default")
      (node (ref "U$1") (pin "PF9") (pinfunction "19_PF9") (pintype "passive"))
    )
    (net (code "98") (name "/PF10") (class "Default")
      (node (ref "U$1") (pin "PF10") (pinfunction "20_PF10") (pintype "passive"))
    )
    (net (code "99") (name "/PF11") (class "Default")
      (node (ref "U$1") (pin "PF11") (pinfunction "41_PF11") (pintype "passive"))
    )
    (net (code "100") (name "/PF12") (class "Default")
      (node (ref "IC1") (pin "43") (pinfunction "A6_43") (pintype "input"))
      (node (ref "U$1") (pin "PF12") (pinfunction "42_PF12") (pintype "passive"))
    )
    (net (code "101") (name "/PF13") (class "Default")
      (node (ref "IC1") (pin "42") (pinfunction "A7_42") (pintype "input"))
      (node (ref "U$1") (pin "PF13") (pinfunction "43_PF13") (pintype "passive"))
    )
    (net (code "102") (name "/PF14") (class "Default")
      (node (ref "IC1") (pin "27") (pinfunction "A8_27") (pintype "input"))
      (node (ref "U$1") (pin "PF14") (pinfunction "44_PF14") (pintype "passive"))
    )
    (net (code "103") (name "/PF15") (class "Default")
      (node (ref "IC1") (pin "26") (pinfunction "A9_26") (pintype "input"))
      (node (ref "U$1") (pin "PF15") (pinfunction "45_PF15") (pintype "passive"))
    )
    (net (code "104") (name "/PG0") (class "Default")
      (node (ref "IC1") (pin "25") (pinfunction "A10_25") (pintype "input"))
      (node (ref "U$1") (pin "PG0") (pinfunction "46_PG0") (pintype "passive"))
    )
    (net (code "105") (name "/PG1") (class "Default")
      (node (ref "IC1") (pin "24") (pinfunction "A11_24") (pintype "input"))
      (node (ref "U$1") (pin "PG1") (pinfunction "47_PG1") (pintype "passive"))
    )
    (net (code "106") (name "/PG2") (class "Default")
      (node (ref "IC1") (pin "22") (pinfunction "A12_22") (pintype "input"))
      (node (ref "U$1") (pin "PG2") (pinfunction "47_PG2") (pintype "passive"))
    )
    (net (code "107") (name "/PG3") (class "Default")
      (node (ref "IC1") (pin "21") (pinfunction "A13_21") (pintype "input"))
      (node (ref "U$1") (pin "PG3") (pinfunction "46_PG3") (pintype "passive"))
    )
    (net (code "108") (name "/PG4") (class "Default")
      (node (ref "IC1") (pin "20") (pinfunction "A14_20") (pintype "input"))
      (node (ref "U$1") (pin "PG4") (pinfunction "45_PG4") (pintype "passive"))
    )
    (net (code "109") (name "/PG5") (class "Default")
      (node (ref "IC1") (pin "19") (pinfunction "A15_19") (pintype "input"))
      (node (ref "U$1") (pin "PG5") (pinfunction "44_PG5") (pintype "passive"))
    )
    (net (code "110") (name "/PG6") (class "Default")
      (node (ref "U$1") (pin "PG6") (pinfunction "43_PG6") (pintype "passive"))
      (node (ref "U$4") (pin "25") (pinfunction "1_25") (pintype "passive"))
    )
    (net (code "111") (name "/PG7") (class "Default")
      (node (ref "R7") (pin "1") (pinfunction "1_1") (pintype "passive"))
      (node (ref "U$1") (pin "PG7") (pinfunction "42_PG7") (pintype "passive"))
      (node (ref "U$5") (pin "CD1") (pinfunction "CARD_DETECT_CD1") (pintype "passive"))
    )
    (net (code "112") (name "/PG8") (class "Default")
      (node (ref "R6") (pin "1") (pinfunction "1_1") (pintype "passive"))
      (node (ref "U$1") (pin "PG8") (pinfunction "41_PG8") (pintype "passive"))
      (node (ref "U$5") (pin "CD2") (pinfunction "CARD_DETECT1_CD2") (pintype "passive"))
    )
    (net (code "113") (name "/PG9") (class "Default")
      (node (ref "IC1") (pin "6") (pinfunction "~{CE}_6") (pintype "input"))
      (node (ref "R10") (pin "1") (pinfunction "1_1") (pintype "passive"))
      (node (ref "U$1") (pin "PG9") (pinfunction "17_PG9") (pintype "passive"))
    )
    (net (code "114") (name "/PG10") (class "Default")
      (node (ref "U$1") (pin "PG10") (pinfunction "16_PG10") (pintype "passive"))
      (node (ref "U$3") (pin "D4") (pinfunction "D4_D4") (pintype "passive"))
    )
    (net (code "115") (name "/PG11") (class "Default")
      (node (ref "U$1") (pin "PG11") (pinfunction "15_PG11") (pintype "passive"))
      (node (ref "U$3") (pin "D5") (pinfunction "D5_D5") (pintype "passive"))
    )
    (net (code "116") (name "/PG12") (class "Default")
      (node (ref "U$1") (pin "PG12") (pinfunction "14_PG12") (pintype "passive"))
    )
    (net (code "117") (name "/PG13") (class "Default")
      (node (ref "U$1") (pin "PG13") (pinfunction "13_PG13") (pintype "passive"))
    )
    (net (code "118") (name "/PG14") (class "Default")
      (node (ref "U$1") (pin "PG14") (pinfunction "12_PG14") (pintype "passive"))
    )
    (net (code "119") (name "/PG15") (class "Default")
      (node (ref "U$1") (pin "PG15") (pinfunction "11_PG15") (pintype "passive"))
    )
    (net (code "120") (name "/PH0") (class "Default")
      (node (ref "U$1") (pin "PH0") (pinfunction "21_PH0") (pintype "passive"))
    )
    (net (code "121") (name "/PH1") (class "Default")
      (node (ref "U$1") (pin "PH1") (pinfunction "22_PH1") (pintype "passive"))
    )
    (net (code "122") (name "/VBAT") (class "Default")
      (node (ref "U$1") (pin "VBAT") (pinfunction "6_VBAT") (pintype "passive"))
    )
    (net (code "123") (name "Net-(R8-Pad1)") (class "Default")
      (node (ref "R8") (pin "1") (pinfunction "1_1") (pintype "passive"))
      (node (ref "T1") (pin "B") (pinfunction "B_B") (pintype "passive"))
    )
    (net (code "124") (name "unconnected-(JP1-5-PadNC)") (class "Default")
      (node (ref "JP1") (pin "NC") (pinfunction "5_NC") (pintype "passive"))
    )
    (net (code "125") (name "unconnected-(JP1-24-PadNC6)") (class "Default")
      (node (ref "JP1") (pin "NC6") (pinfunction "24_NC6") (pintype "passive"))
    )
    (net (code "126") (name "unconnected-(JP1-31-PadF_CS)") (class "Default")
      (node (ref "JP1") (pin "F_CS") (pinfunction "31_F_CS") (pintype "passive"))
    )
    (net (code "127") (name "unconnected-(JP1-35-PadNC2)") (class "Default")
      (node (ref "JP1") (pin "NC2") (pinfunction "35_NC2") (pintype "passive"))
    )
    (net (code "128") (name "unconnected-(JP1-38-PadNC5)") (class "Default")
      (node (ref "JP1") (pin "NC5") (pinfunction "38_NC5") (pintype "passive"))
    )
    (net (code "129") (name "unconnected-(JP1-39-PadNC3)") (class "Default")
      (node (ref "JP1") (pin "NC3") (pinfunction "39_NC3") (pintype "passive"))
    )
    (net (code "130") (name "unconnected-(JP1-40-PadNC4)") (class "Default")
      (node (ref "JP1") (pin "NC4") (pinfunction "40_NC4") (pintype "passive"))
    )
  )
)
